# ThrusterBatteryMonitor.net
KiCad netlist of a schematic drawn in Altium Designer
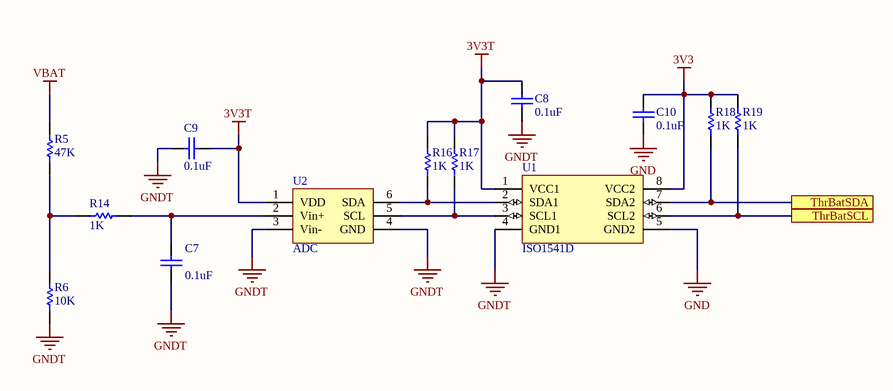
[diagram p0: ThrusterBatteryMonitor.SchDoc]

(export (version "E")
  (design (tool "Eeschema 10.0.6"))
  (components
    (comp (ref "C7")
      (value "0.1uF")
      (footprint "CAPC1608X97X38NL12T08")
      (description "CAP CER 0.1UF 25V X7R 0603")
      (fields (field (name "MANUFACTURER") "Vitramon") (field (name "PART NUMBER") "VJ0603Y-104KXXAC"))
      (libsource (lib "Main") (part "VJ0603Y104KXXAC"))
    )
    (comp (ref "C8")
      (value "0.1uF")
      (footprint "CAPC1608X97X38NL12T08")
      (description "CAP CER 0.1UF 25V X7R 0603")
      (fields (field (name "MANUFACTURER") "Vitramon") (field (name "PART NUMBER") "VJ0603Y-104KXXAC"))
      (libsource (lib "Main") (part "VJ0603Y104KXXAC"))
    )
    (comp (ref "C9")
      (value "0.1uF")
      (footprint "CAPC1608X97X38NL12T08")
      (description "CAP CER 0.1UF 25V X7R 0603")
      (fields (field (name "MANUFACTURER") "Vitramon") (field (name "PART NUMBER") "VJ0603Y-104KXXAC"))
      (libsource (lib "Main") (part "VJ0603Y104KXXAC"))
    )
    (comp (ref "C10")
      (value "0.1uF")
      (footprint "CAPC1608X97X38NL12T08")
      (description "CAP CER 0.1UF 25V X7R 0603")
      (fields (field (name "MANUFACTURER") "Vitramon") (field (name "PART NUMBER") "VJ0603Y-104KXXAC"))
      (libsource (lib "Main") (part "VJ0603Y104KXXAC"))
    )
    (comp (ref "R5")
      (value "47K")
      (footprint "RESC1609X55X30NL10T20")
      (description "RES 47K OHM 0.1% 1/8W 0603")
      (fields (field (name "TOLERANCE") "1%"))
      (libsource (lib "Main") (part "TNPW060347K0BEEA"))
    )
    (comp (ref "R6")
      (value "10K")
      (footprint "RESC1609X55X30NL10T20")
      (description "RES 10K OHM 0.1% 1/8W 0603")
      (fields (field (name "TOLERANCE") "1%"))
      (libsource (lib "Main") (part "TNPW060310K0BEEA"))
    )
    (comp (ref "R14")
      (value "1K")
      (footprint "RESC1609X55X30NL10T20")
      (description "RES 1K OHM 0.1% 1/8W 0603")
      (fields (field (name "TOLERANCE") "1%"))
      (libsource (lib "Main") (part "TNPW06031K00BEEA"))
    )
    (comp (ref "R16")
      (value "1K")
      (footprint "RESC1609X55X30NL10T20")
      (description "RES 1K OHM 0.1% 1/8W 0603")
      (fields (field (name "TOLERANCE") "1%"))
      (libsource (lib "Main") (part "TNPW06031K00BEEA"))
    )
    (comp (ref "R17")
      (value "1K")
      (footprint "RESC1609X55X30NL10T20")
      (description "RES 1K OHM 0.1% 1/8W 0603")
      (fields (field (name "TOLERANCE") "1%"))
      (libsource (lib "Main") (part "TNPW06031K00BEEA"))
    )
    (comp (ref "R18")
      (value "1K")
      (footprint "RESC1609X55X30NL10T20")
      (description "RES 1K OHM 0.1% 1/8W 0603")
      (fields (field (name "TOLERANCE") "1%"))
      (libsource (lib "Main") (part "TNPW06031K00BEEA"))
    )
    (comp (ref "R19")
      (value "1K")
      (footprint "RESC1609X55X30NL10T20")
      (description "RES 1K OHM 0.1% 1/8W 0603")
      (fields (field (name "TOLERANCE") "1%"))
      (libsource (lib "Main") (part "TNPW06031K00BEEA"))
    )
    (comp (ref "U1")
      (value "ISO1541D")
      (footprint "ISO1541D")
      (description "I²C Digital Isolator 2500Vrms 2 Channel 1Mbps 25kV/µs CMTI 8-SOIC (0.154\", 3.90mm Width)")
      (fields (field (name "MANUFACTURER") "Texas Instruments"))
      (libsource (lib "Main") (part "ISO1541D"))
    )
    (comp (ref "U2")
      (value "ADC")
      (footprint "SOT95P280X145-6N")
      (description "12 Bit Analog to Digital Converter 2, 4 Input 1 Sigma-Delta 10-VSSOP")
      (libsource (lib "Main") (part "ADS1000A0IDBVT"))
    )
  )
  (nets
    (net (code "1") (name "/ThrBatSCL") (class "Default")
      (node (ref "R19") (pin "1") (pinfunction "1_1") (pintype "passive"))
      (node (ref "U1") (pin "6") (pinfunction "SCL2_6") (pintype "bidirectional"))
    )
    (net (code "2") (name "/ThrBatSDA") (class "Default")
      (node (ref "R18") (pin "1") (pinfunction "1_1") (pintype "passive"))
      (node (ref "U1") (pin "7") (pinfunction "SDA2_7") (pintype "bidirectional"))
    )
    (net (code "3") (name "3V3") (class "Default")
      (node (ref "C10") (pin "2") (pinfunction "2_2") (pintype "passive"))
      (node (ref "R18") (pin "2") (pinfunction "2_2") (pintype "passive"))
      (node (ref "R19") (pin "2") (pinfunction "2_2") (pintype "passive"))
      (node (ref "U1") (pin "8") (pinfunction "VCC2_8") (pintype "power_in"))
    )
    (net (code "4") (name "3V3T") (class "Default")
      (node (ref "C8") (pin "2") (pinfunction "2_2") (pintype "passive"))
      (node (ref "C9") (pin "1") (pinfunction "1_1") (pintype "passive"))
      (node (ref "R16") (pin "2") (pinfunction "2_2") (pintype "passive"))
      (node (ref "R17") (pin "2") (pinfunction "2_2") (pintype "passive"))
      (node (ref "U1") (pin "1") (pinfunction "VCC1_1") (pintype "power_in"))
      (node (ref "U2") (pin "1") (pinfunction "VDD_1") (pintype "passive"))
    )
    (net (code "5") (name "GND") (class "Default")
      (node (ref "C10") (pin "1") (pinfunction "1_1") (pintype "passive"))
      (node (ref "U1") (pin "5") (pinfunction "GND2_5") (pintype "power_in"))
    )
    (net (code "6") (name "GNDT") (class "Default")
      (node (ref "C7") (pin "1") (pinfunction "1_1") (pintype "passive"))
      (node (ref "C8") (pin "1") (pinfunction "1_1") (pintype "passive"))
      (node (ref "C9") (pin "2") (pinfunction "2_2") (pintype "passive"))
      (node (ref "R6") (pin "1") (pinfunction "1_1") (pintype "passive"))
      (node (ref "U1") (pin "4") (pinfunction "GND1_4") (pintype "power_in"))
      (node (ref "U2") (pin "3") (pinfunction "Vin-_3") (pintype "passive"))
      (node (ref "U2") (pin "4") (pinfunction "GND_4") (pintype "passive"))
    )
    (net (code "7") (name "Net-(R14-Pad1)") (class "Default")
      (node (ref "R14") (pin "1") (pinfunction "1_1") (pintype "passive"))
      (node (ref "R5") (pin "1") (pinfunction "1_1") (pintype "passive"))
      (node (ref "R6") (pin "2") (pinfunction "2_2") (pintype "passive"))
    )
    (net (code "8") (name "Net-(U1-SCL1)") (class "Default")
      (node (ref "R17") (pin "1") (pinfunction "1_1") (pintype "passive"))
      (node (ref "U1") (pin "3") (pinfunction "SCL1_3") (pintype "bidirectional"))
      (node (ref "U2") (pin "5") (pinfunction "SCL_5") (pintype "passive"))
    )
    (net (code "9") (name "Net-(U1-SDA1)") (class "Default")
      (node (ref "R16") (pin "1") (pinfunction "1_1") (pintype "passive"))
      (node (ref "U1") (pin "2") (pinfunction "SDA1_2") (pintype "bidirectional"))
      (node (ref "U2") (pin "6") (pinfunction "SDA_6") (pintype "passive"))
    )
    (net (code "10") (name "Net-(U2-Vin+)") (class "Default")
      (node (ref "C7") (pin "2") (pinfunction "2_2") (pintype "passive"))
      (node (ref "R14") (pin "2") (pinfunction "2_2") (pintype "passive"))
      (node (ref "U2") (pin "2") (pinfunction "Vin+_2") (pintype "passive"))
    )
    (net (code "11") (name "VBAT") (class "Default")
      (node (ref "R5") (pin "2") (pinfunction "2_2") (pintype "passive"))
    )
  )
)
